# breakout.net
KiCad netlist of a schematic drawn in EAGLE
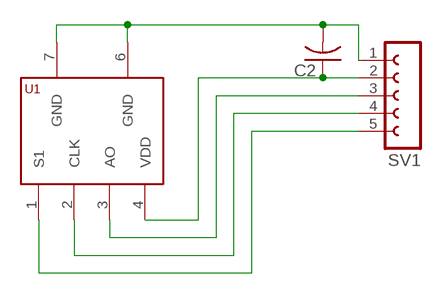
[diagram p0: schematic, sheet 1]

(export (version "E")
  (design (tool "Eeschema 10.0.6"))
  (components
    (comp (ref "C2")
      (value "C-US025-030X050")
      (footprint "eagle-import:C025-030X050")
      (libsource (lib "eagle-import") (part "C-US025-030X050"))
    )
    (comp (ref "SV1")
      (value "FE05-1")
      (footprint "eagle-import:FE05-1")
      (libsource (lib "eagle-import") (part "FE05-1"))
    )
    (comp (ref "U1")
      (value "TSL1401CL")
      (footprint "eagle-import:TSL8")
      (libsource (lib "eagle-import") (part "TSL1401CL"))
    )
  )
  (nets
    (net (code "1") (name "Net-(C2-Pad2)") (class "Default")
      (node (ref "C2") (pin "2") (pinfunction "2_2") (pintype "passive"))
      (node (ref "SV1") (pin "1") (pinfunction "1_1") (pintype "passive"))
      (node (ref "U1") (pin "6") (pinfunction "GND_6") (pintype "input"))
      (node (ref "U1") (pin "7") (pinfunction "GND_7") (pintype "input"))
    )
    (net (code "2") (name "Net-(U1-AO)") (class "Default")
      (node (ref "SV1") (pin "3") (pinfunction "3_3") (pintype "passive"))
      (node (ref "U1") (pin "3") (pinfunction "AO_3") (pintype "input"))
    )
    (net (code "3") (name "Net-(U1-CLK)") (class "Default")
      (node (ref "SV1") (pin "4") (pinfunction "4_4") (pintype "passive"))
      (node (ref "U1") (pin "2") (pinfunction "CLK_2") (pintype "input"))
    )
    (net (code "4") (name "Net-(U1-S1)") (class "Default")
      (node (ref "SV1") (pin "5") (pinfunction "5_5") (pintype "passive"))
      (node (ref "U1") (pin "1") (pinfunction "S1_1") (pintype "input"))
    )
    (net (code "5") (name "Net-(U1-VDD)") (class "Default")
      (node (ref "C2") (pin "1") (pinfunction "1_1") (pintype "passive"))
      (node (ref "SV1") (pin "2") (pinfunction "2_2") (pintype "passive"))
      (node (ref "U1") (pin "4") (pinfunction "VDD_4") (pintype "input"))
    )
  )
)
